# MCU.net
KiCad netlist of a schematic drawn in Altium Designer
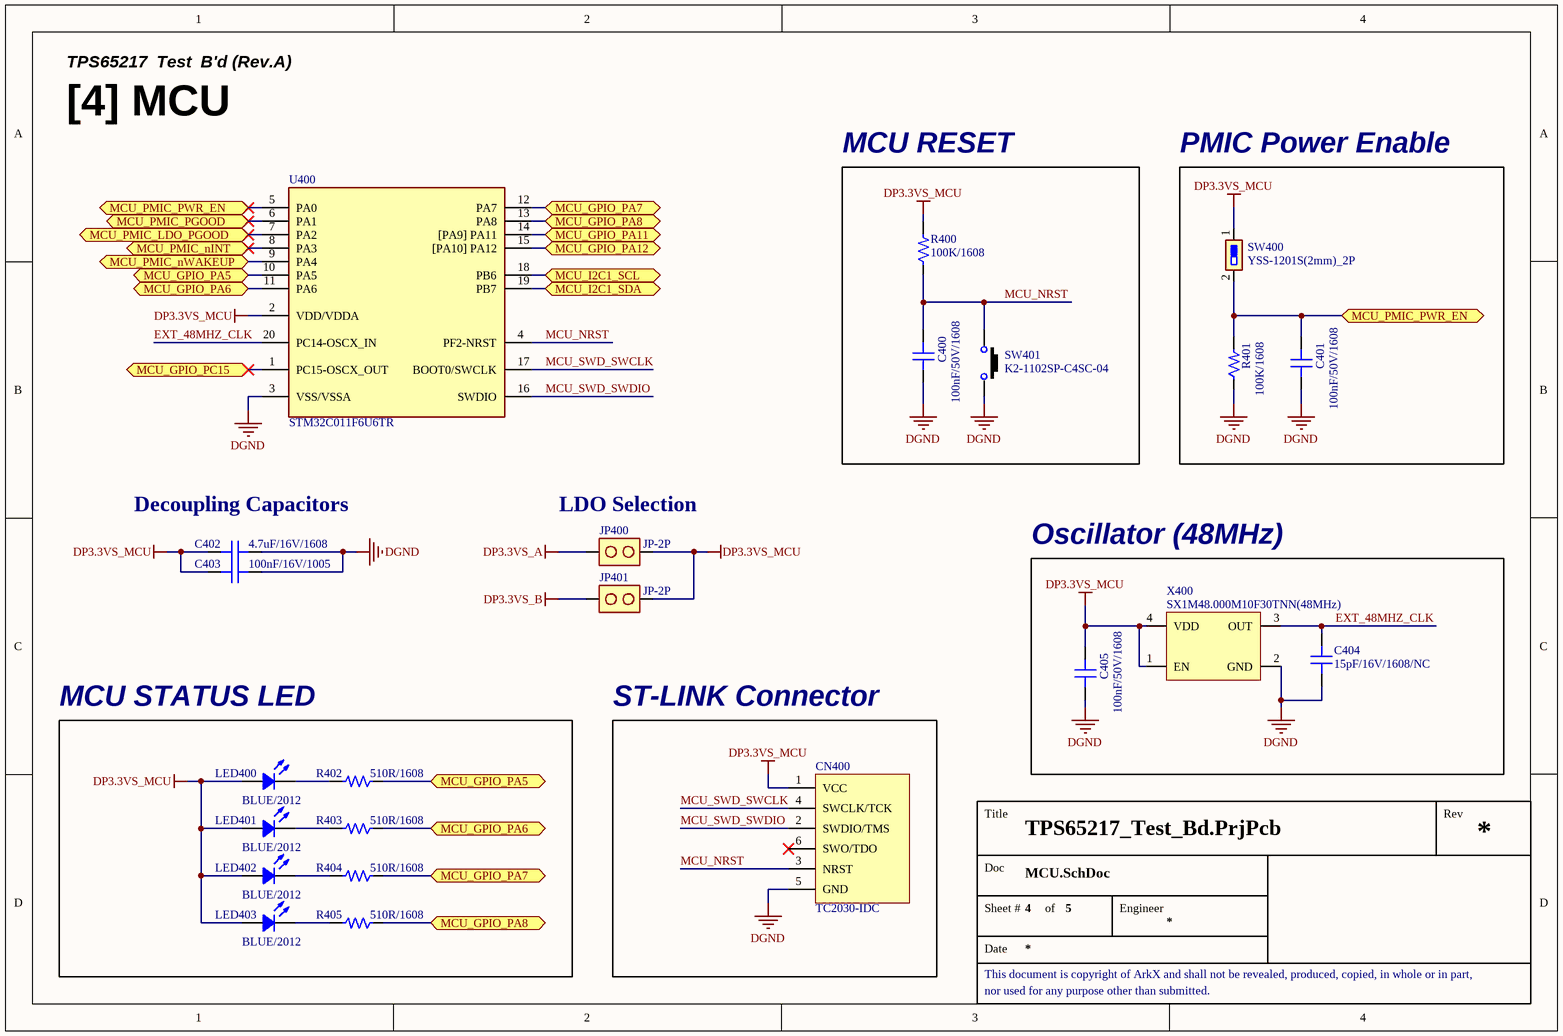
[diagram p0: MCU.SchDoc]

(export (version "E")
  (design (tool "Eeschema 10.0.6"))
  (components
    (comp (ref "C400")
      (value "100nF/50V/1608")
      (footprint "CAP 1608 (0603_INCH)")
      (description "Ceramic CAP_100nF/50V/1608")
      (fields (field (name "LCSC PART #") "C14663"))
      (libsource (lib "Arkx") (part "CAP_100nF/50V/1608"))
    )
    (comp (ref "C401")
      (value "100nF/50V/1608")
      (footprint "CAP 1608 (0603_INCH)")
      (description "Ceramic CAP_100nF/50V/1608")
      (fields (field (name "LCSC PART #") "C14663"))
      (libsource (lib "Arkx") (part "CAP_100nF/50V/1608"))
    )
    (comp (ref "C402")
      (value "4.7uF/16V/1608")
      (footprint "CAP 1608 (0603_INCH)")
      (description "Ceramic CAP_4.7uF/16V/1608")
      (fields (field (name "LCSC PART #") "C19666"))
      (libsource (lib "Arkx") (part "CAP_4.7uF/16V/1608"))
    )
    (comp (ref "C403")
      (value "100nF/16V/1005")
      (footprint "CAP 1005 (0402_INCH)")
      (description "Ceramic CAP_100nF/16V/1005")
      (fields (field (name "LCSC PART #") "C1525"))
      (libsource (lib "Arkx") (part "CAP_100nF/16V/1005"))
    )
    (comp (ref "C404")
      (value "15pF/16V/1608/NC")
      (footprint "CAP 1608 (0603_INCH)/NC")
      (description "Ceramic CAP_15pF/16V/1608")
      (libsource (lib "Arkx") (part "CAP_NC_15pF/16V/1608"))
    )
    (comp (ref "C405")
      (value "100nF/50V/1608")
      (footprint "CAP 1608 (0603_INCH)")
      (description "Ceramic CAP_100nF/50V/1608")
      (fields (field (name "LCSC PART #") "C14663"))
      (libsource (lib "Arkx") (part "CAP_100nF/50V/1608"))
    )
    (comp (ref "CN400")
      (value "TC2030-IDC")
      (footprint "CON_TC2030-IDC")
      (description "Tag-Connect No-Solder SWD Debug Connector DO NOT PLACE")
      (fields (field (name "MANUFACTURER") "Tag-Connect") (field (name "MANUFACTURER PART NUMBER") "TC2030"))
      (libsource (lib "Arkx") (part "CON_TC2030-IDC(ST-LINK)"))
    )
    (comp (ref "JP400")
      (value "JP-2P")
      (footprint "CON PIN_HEADER-2PIN(2.54MM)")
      (libsource (lib "Arkx") (part "CON_JP-2P"))
    )
    (comp (ref "JP401")
      (value "JP-2P")
      (footprint "CON PIN_HEADER-2PIN(2.54MM)")
      (libsource (lib "Arkx") (part "CON_JP-2P"))
    )
    (comp (ref "LED400")
      (value "BLUE/2012")
      (footprint "LED MHT170RGBCT (BLUE)")
      (fields (field (name "LCSC PART #") "C2962094"))
      (libsource (lib "Arkx") (part "LED_MHT170RGBCT(BLUE)"))
    )
    (comp (ref "LED401")
      (value "BLUE/2012")
      (footprint "LED MHT170RGBCT (BLUE)")
      (fields (field (name "LCSC PART #") "C2962094"))
      (libsource (lib "Arkx") (part "LED_MHT170RGBCT(BLUE)"))
    )
    (comp (ref "LED402")
      (value "BLUE/2012")
      (footprint "LED MHT170RGBCT (BLUE)")
      (fields (field (name "LCSC PART #") "C2962094"))
      (libsource (lib "Arkx") (part "LED_MHT170RGBCT(BLUE)"))
    )
    (comp (ref "LED403")
      (value "BLUE/2012")
      (footprint "LED MHT170RGBCT (BLUE)")
      (fields (field (name "LCSC PART #") "C2962094"))
      (libsource (lib "Arkx") (part "LED_MHT170RGBCT(BLUE)"))
    )
    (comp (ref "R400")
      (value "100K/1608")
      (footprint "RES 1608 (0603_inch)")
      (description "RES_100K/1608/0.1W")
      (fields (field (name "LCSC PART #") "C25803"))
      (libsource (lib "Arkx") (part "RES_100K/1608/0.1W"))
    )
    (comp (ref "R401")
      (value "100K/1608")
      (footprint "RES 1608 (0603_inch)")
      (description "RES_100K/1608/0.1W")
      (fields (field (name "LCSC PART #") "C25803"))
      (libsource (lib "Arkx") (part "RES_100K/1608/0.1W"))
    )
    (comp (ref "R402")
      (value "510R/1608")
      (footprint "RES 1608 (0603_inch)")
      (description "RES_510R/1608/0.1W")
      (fields (field (name "LCSC PART #") "C23193"))
      (libsource (lib "Arkx") (part "RES_510R/1608/0.1W"))
    )
    (comp (ref "R403")
      (value "510R/1608")
      (footprint "RES 1608 (0603_inch)")
      (description "RES_510R/1608/0.1W")
      (fields (field (name "LCSC PART #") "C23193"))
      (libsource (lib "Arkx") (part "RES_510R/1608/0.1W"))
    )
    (comp (ref "R404")
      (value "510R/1608")
      (footprint "RES 1608 (0603_inch)")
      (description "RES_510R/1608/0.1W")
      (fields (field (name "LCSC PART #") "C23193"))
      (libsource (lib "Arkx") (part "RES_510R/1608/0.1W"))
    )
    (comp (ref "R405")
      (value "510R/1608")
      (footprint "RES 1608 (0603_inch)")
      (description "RES_510R/1608/0.1W")
      (fields (field (name "LCSC PART #") "C23193"))
      (libsource (lib "Arkx") (part "RES_510R/1608/0.1W"))
    )
    (comp (ref "SW400")
      (value "YSS-1201S(2mm)_2P")
      (footprint "SW YSS-1201S-2mm")
      (description "SMD Slide Switch.\r\nRating : DC 6V/0.3A\r\nTravel : 2MM")
      (libsource (lib "Arkx") (part "SW_YSS-1201S(2mm)_2P"))
    )
    (comp (ref "SW401")
      (value "K2-1102SP-C4SC-04")
      (footprint "SW K2-1102SP-C4SC-04")
      (fields (field (name "LCSC PART #") "C127509"))
      (libsource (lib "Arkx") (part "SW_K2-1102SP-C4SC-04(2P)"))
    )
    (comp (ref "U400")
      (value "STM32C011F6U6TR")
      (footprint "IC_UFQFPN-20")
      (description "ARM® Cortex®-M0+ STM32C0 Microcontroller IC 32-Bit 48MHz 32KB (32K x 8) FLASH 20-UFQFPN (3x3)")
      (fields (field (name "MANUFACTURER") "STMicroelectronics") (field (name "LCSC PART #") "C5456206"))
      (libsource (lib "Arkx") (part "IC_MCU_STM32C011F6U6TR"))
    )
    (comp (ref "X400")
      (value "SX1M48.000M10F30TNN(48MHz)")
      (footprint "OSC_SMD2016-4P")
      (description "1.62V~3.63V ±10ppm CMOS 48MHz SMD2016-4P  Oscillators ROHS")
      (fields (field (name "LCSC PART #") "C2901617"))
      (libsource (lib "Arkx") (part "OSC_SX1M48.000M10F30TNN(48MHz)"))
    )
  )
  (nets
    (net (code "1") (name "/EXT_48MHZ_CLK") (class "Default")
      (node (ref "C404") (pin "2") (pinfunction "2_2") (pintype "passive"))
      (node (ref "U400") (pin "20") (pinfunction "PC14-OSCX_IN_20") (pintype "passive"))
      (node (ref "X400") (pin "3") (pinfunction "OUT_3") (pintype "passive"))
    )
    (net (code "2") (name "/MCU_GPIO_PA5") (class "Default")
      (node (ref "R402") (pin "1") (pinfunction "1_1") (pintype "passive"))
      (node (ref "U400") (pin "10") (pinfunction "PA5_10") (pintype "passive"))
    )
    (net (code "3") (name "/MCU_GPIO_PA6") (class "Default")
      (node (ref "R403") (pin "1") (pinfunction "1_1") (pintype "passive"))
      (node (ref "U400") (pin "11") (pinfunction "PA6_11") (pintype "passive"))
    )
    (net (code "4") (name "/MCU_GPIO_PA7") (class "Default")
      (node (ref "R404") (pin "1") (pinfunction "1_1") (pintype "passive"))
      (node (ref "U400") (pin "12") (pinfunction "PA7_12") (pintype "passive"))
    )
    (net (code "5") (name "/MCU_GPIO_PA8") (class "Default")
      (node (ref "R405") (pin "1") (pinfunction "1_1") (pintype "passive"))
      (node (ref "U400") (pin "13") (pinfunction "PA8_13") (pintype "passive"))
    )
    (net (code "6") (name "/MCU_GPIO_PA11") (class "Default")
      (node (ref "U400") (pin "14") (pinfunction "[PA9]_PA11_14") (pintype "passive"))
    )
    (net (code "7") (name "/MCU_GPIO_PA12") (class "Default")
      (node (ref "U400") (pin "15") (pinfunction "[PA10]_PA12_15") (pintype "passive"))
    )
    (net (code "8") (name "/MCU_GPIO_PC15") (class "Default")
      (node (ref "U400") (pin "1") (pinfunction "PC15-OSCX_OUT_1") (pintype "passive+no_connect"))
    )
    (net (code "9") (name "/MCU_I2C1_SCL") (class "Default")
      (node (ref "U400") (pin "18") (pinfunction "PB6_18") (pintype "passive"))
    )
    (net (code "10") (name "/MCU_I2C1_SDA") (class "Default")
      (node (ref "U400") (pin "19") (pinfunction "PB7_19") (pintype "passive"))
    )
    (net (code "11") (name "/MCU_NRST") (class "Default")
      (node (ref "C400") (pin "2") (pinfunction "2_2") (pintype "passive"))
      (node (ref "CN400") (pin "3") (pinfunction "NRST_3") (pintype "passive"))
      (node (ref "R400") (pin "1") (pinfunction "1_1") (pintype "passive"))
      (node (ref "SW401") (pin "1") (pinfunction "1_1") (pintype "passive"))
      (node (ref "U400") (pin "4") (pinfunction "PF2-NRST_4") (pintype "passive"))
    )
    (net (code "12") (name "/MCU_PMIC_LDO_PGOOD") (class "Default")
      (node (ref "U400") (pin "7") (pinfunction "PA2_7") (pintype "passive+no_connect"))
    )
    (net (code "13") (name "/MCU_PMIC_PGOOD") (class "Default")
      (node (ref "U400") (pin "6") (pinfunction "PA1_6") (pintype "passive+no_connect"))
    )
    (net (code "14") (name "/MCU_PMIC_PWR_EN") (class "Default")
      (node (ref "C401") (pin "2") (pinfunction "2_2") (pintype "passive"))
      (node (ref "R401") (pin "2") (pinfunction "2_2") (pintype "passive"))
      (node (ref "SW400") (pin "2") (pinfunction "2_2") (pintype "passive"))
      (node (ref "U400") (pin "5") (pinfunction "PA0_5") (pintype "passive"))
    )
    (net (code "15") (name "/MCU_PMIC_nINT") (class "Default")
      (node (ref "U400") (pin "8") (pinfunction "PA3_8") (pintype "passive+no_connect"))
    )
    (net (code "16") (name "/MCU_PMIC_nWAKEUP") (class "Default")
      (node (ref "U400") (pin "9") (pinfunction "PA4_9") (pintype "passive"))
    )
    (net (code "17") (name "/MCU_SWD_SWCLK") (class "Default")
      (node (ref "CN400") (pin "4") (pinfunction "SWCLK/TCK_4") (pintype "passive"))
      (node (ref "U400") (pin "17") (pinfunction "BOOT0/SWCLK_17") (pintype "passive"))
    )
    (net (code "18") (name "/MCU_SWD_SWDIO") (class "Default")
      (node (ref "CN400") (pin "2") (pinfunction "SWDIO/TMS_2") (pintype "passive"))
      (node (ref "U400") (pin "16") (pinfunction "SWDIO_16") (pintype "passive"))
    )
    (net (code "19") (name "DGND") (class "Default")
      (node (ref "C400") (pin "1") (pinfunction "1_1") (pintype "passive"))
      (node (ref "C401") (pin "1") (pinfunction "1_1") (pintype "passive"))
      (node (ref "C402") (pin "1") (pinfunction "1_1") (pintype "passive"))
      (node (ref "C403") (pin "1") (pinfunction "1_1") (pintype "passive"))
      (node (ref "C404") (pin "1") (pinfunction "1_1") (pintype "passive"))
      (node (ref "C405") (pin "1") (pinfunction "1_1") (pintype "passive"))
      (node (ref "CN400") (pin "5") (pinfunction "GND_5") (pintype "passive"))
      (node (ref "R401") (pin "1") (pinfunction "1_1") (pintype "passive"))
      (node (ref "SW401") (pin "3") (pinfunction "3_3") (pintype "passive"))
      (node (ref "U400") (pin "3") (pinfunction "VSS/VSSA_3") (pintype "passive"))
      (node (ref "X400") (pin "2") (pinfunction "GND_2") (pintype "passive"))
    )
    (net (code "20") (name "DP3.3VS_A") (class "Default")
      (node (ref "JP400") (pin "1") (pinfunction "1_1") (pintype "passive"))
    )
    (net (code "21") (name "DP3.3VS_B") (class "Default")
      (node (ref "JP401") (pin "1") (pinfunction "1_1") (pintype "passive"))
    )
    (net (code "22") (name "DP3.3VS_MCU") (class "Default")
      (node (ref "C402") (pin "2") (pinfunction "2_2") (pintype "passive"))
      (node (ref "C403") (pin "2") (pinfunction "2_2") (pintype "passive"))
      (node (ref "C405") (pin "2") (pinfunction "2_2") (pintype "passive"))
      (node (ref "CN400") (pin "1") (pinfunction "VCC_1") (pintype "passive"))
      (node (ref "JP400") (pin "2") (pinfunction "2_2") (pintype "passive"))
      (node (ref "JP401") (pin "2") (pinfunction "2_2") (pintype "passive"))
      (node (ref "LED400") (pin "4") (pinfunction "Common_Anode_4") (pintype "passive"))
      (node (ref "LED401") (pin "4") (pinfunction "Common_Anode_4") (pintype "passive"))
      (node (ref "LED402") (pin "4") (pinfunction "Common_Anode_4") (pintype "passive"))
      (node (ref "LED403") (pin "4") (pinfunction "Common_Anode_4") (pintype "passive"))
      (node (ref "R400") (pin "2") (pinfunction "2_2") (pintype "passive"))
      (node (ref "SW400") (pin "1") (pinfunction "1_1") (pintype "passive"))
      (node (ref "U400") (pin "2") (pinfunction "VDD/VDDA_2") (pintype "passive"))
      (node (ref "X400") (pin "1") (pinfunction "EN_1") (pintype "passive"))
      (node (ref "X400") (pin "4") (pinfunction "VDD_4") (pintype "passive"))
    )
    (net (code "23") (name "Net-(LED400-BLUE)") (class "Default")
      (node (ref "LED400") (pin "3") (pinfunction "BLUE_3") (pintype "passive"))
      (node (ref "R402") (pin "2") (pinfunction "2_2") (pintype "passive"))
    )
    (net (code "24") (name "Net-(LED401-BLUE)") (class "Default")
      (node (ref "LED401") (pin "3") (pinfunction "BLUE_3") (pintype "passive"))
      (node (ref "R403") (pin "2") (pinfunction "2_2") (pintype "passive"))
    )
    (net (code "25") (name "Net-(LED402-BLUE)") (class "Default")
      (node (ref "LED402") (pin "3") (pinfunction "BLUE_3") (pintype "passive"))
      (node (ref "R404") (pin "2") (pinfunction "2_2") (pintype "passive"))
    )
    (net (code "26") (name "Net-(LED403-BLUE)") (class "Default")
      (node (ref "LED403") (pin "3") (pinfunction "BLUE_3") (pintype "passive"))
      (node (ref "R405") (pin "2") (pinfunction "2_2") (pintype "passive"))
    )
    (net (code "27") (name "unconnected-(CN400-SWO{slash}TDO-Pad6)") (class "Default")
      (node (ref "CN400") (pin "6") (pinfunction "SWO/TDO_6") (pintype "passive+no_connect"))
    )
  )
)
